# PickupDaughterBoard.net
KiCad netlist of a schematic drawn in EAGLE
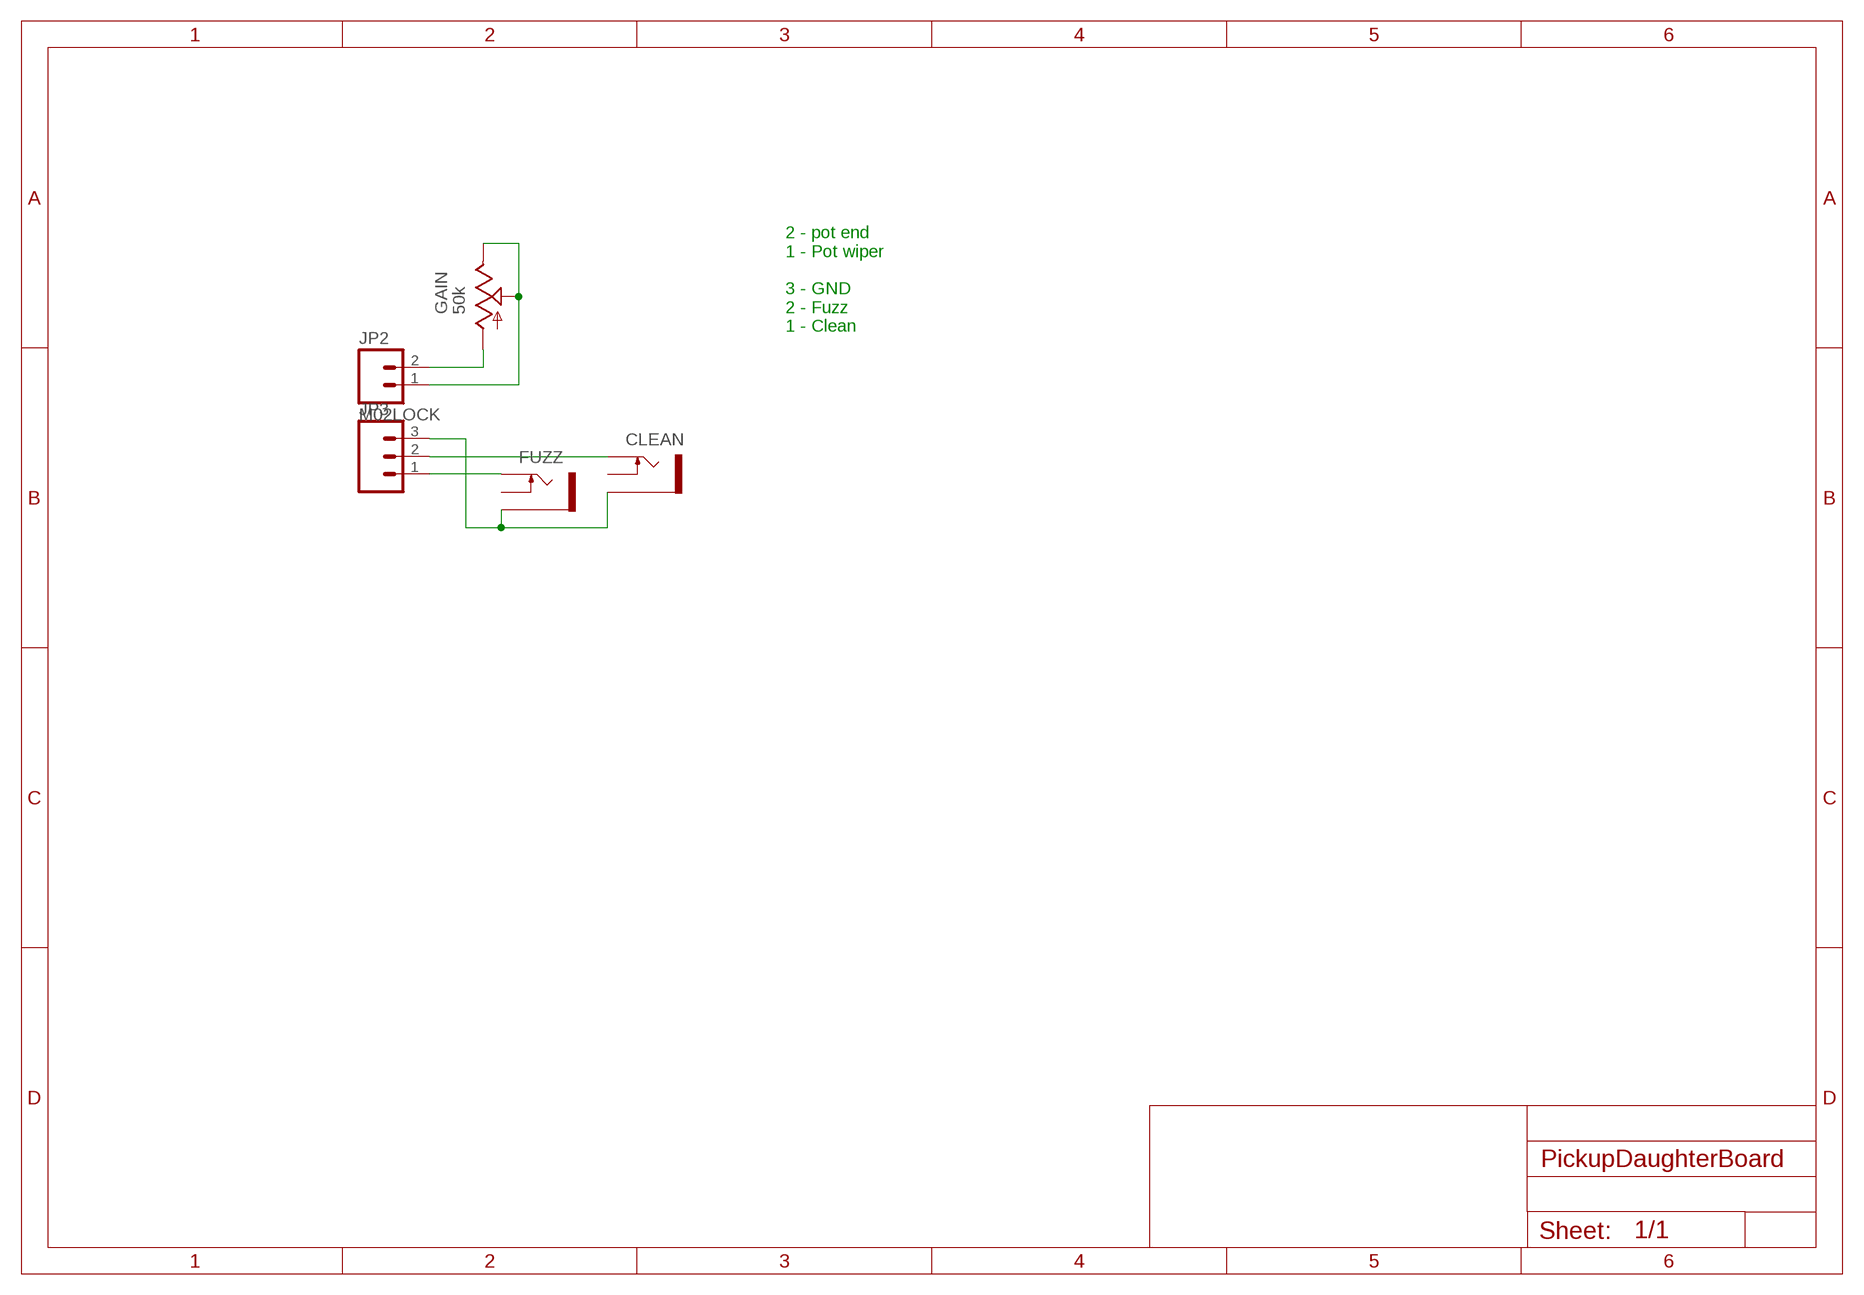
[diagram p0: schematic, sheet 1]

(export (version "E")
  (design (tool "Eeschema 10.0.6"))
  (components
    (comp (ref "CLEAN")
      (value "THONKICONNNEW")
      (footprint "eagle-import:WQP-PJ301M-12_JACK")
      (libsource (lib "eagle-import") (part "THONKICONNNEW"))
    )
    (comp (ref "FUZZ")
      (value "THONKICONNNEW")
      (footprint "eagle-import:WQP-PJ301M-12_JACK")
      (libsource (lib "eagle-import") (part "THONKICONNNEW"))
    )
    (comp (ref "GAIN")
      (value "50k")
      (footprint "eagle-import:EVUF")
      (libsource (lib "eagle-import") (part "ALPHA-9MMAF2"))
    )
    (comp (ref "JP2")
      (value "M02LOCK")
      (footprint "eagle-import:1X02_LOCK")
      (libsource (lib "eagle-import") (part "M02LOCK"))
    )
    (comp (ref "JP3")
      (value "M03LOCK")
      (footprint "eagle-import:1X03_LOCK")
      (libsource (lib "eagle-import") (part "M03LOCK"))
    )
  )
  (nets
    (net (code "1") (name "Net-(CLEAN-SLEEVE)") (class "Default")
      (node (ref "CLEAN") (pin "P$3_SLEEVE") (pinfunction "SLEEVE_P$3_SLEEVE") (pintype "passive"))
      (node (ref "FUZZ") (pin "P$3_SLEEVE") (pinfunction "SLEEVE_P$3_SLEEVE") (pintype "passive"))
      (node (ref "JP3") (pin "3") (pinfunction "3_3") (pintype "passive"))
    )
    (net (code "2") (name "Net-(CLEAN-TIP)") (class "Default")
      (node (ref "CLEAN") (pin "P$1_TIP") (pinfunction "TIP_P$1_TIP") (pintype "passive"))
      (node (ref "JP3") (pin "2") (pinfunction "2_2") (pintype "passive"))
    )
    (net (code "3") (name "Net-(FUZZ-TIP)") (class "Default")
      (node (ref "FUZZ") (pin "P$1_TIP") (pinfunction "TIP_P$1_TIP") (pintype "passive"))
      (node (ref "JP3") (pin "1") (pinfunction "1_1") (pintype "passive"))
    )
    (net (code "4") (name "Net-(GAIN-A)") (class "Default")
      (node (ref "GAIN") (pin "1") (pinfunction "A_1") (pintype "passive"))
      (node (ref "JP2") (pin "2") (pinfunction "2_2") (pintype "passive"))
    )
    (net (code "5") (name "Net-(GAIN-E)") (class "Default")
      (node (ref "GAIN") (pin "2") (pinfunction "S_2") (pintype "passive"))
      (node (ref "GAIN") (pin "3") (pinfunction "E_3") (pintype "passive"))
      (node (ref "JP2") (pin "1") (pinfunction "1_1") (pintype "passive"))
    )
    (net (code "6") (name "unconnected-(CLEAN-SWITCH-PadP$2_SWITCH)") (class "Default")
      (node (ref "CLEAN") (pin "P$2_SWITCH") (pinfunction "SWITCH_P$2_SWITCH") (pintype "passive"))
    )
    (net (code "7") (name "unconnected-(FUZZ-SWITCH-PadP$2_SWITCH)") (class "Default")
      (node (ref "FUZZ") (pin "P$2_SWITCH") (pinfunction "SWITCH_P$2_SWITCH") (pintype "passive"))
    )
  )
)
